# SalinityExpansion.net
KiCad netlist of a schematic drawn in EAGLE
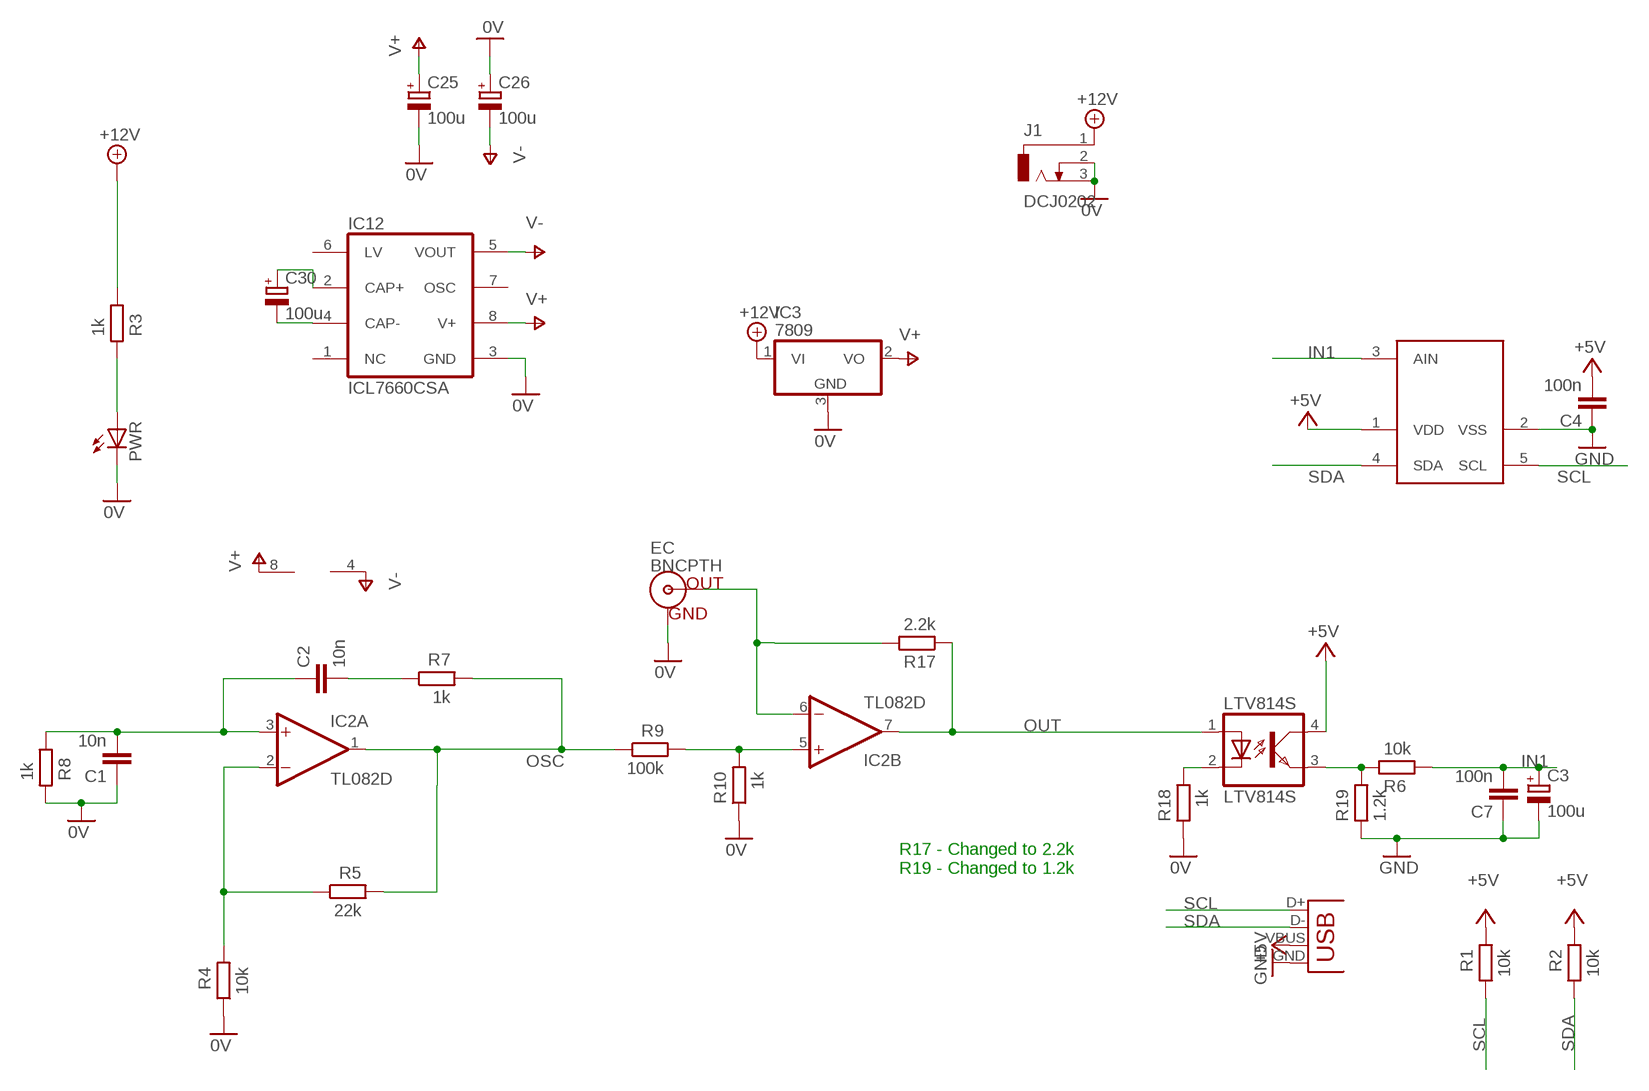
[diagram p0: schematic, sheet 1]

(export (version "E")
  (design (tool "Eeschema 10.0.6"))
  (components
    (comp (ref "C1")
      (value "10n")
      (footprint "eagle-import:C0805K")
      (libsource (lib "eagle-import") (part "C-EUC0805K"))
    )
    (comp (ref "C2")
      (value "10n")
      (footprint "eagle-import:C0805K")
      (libsource (lib "eagle-import") (part "C-EUC0805K"))
    )
    (comp (ref "C3")
      (value "100u")
      (footprint "eagle-import:PANASONIC_D")
      (libsource (lib "eagle-import") (part "CPOL-EUD"))
    )
    (comp (ref "C4")
      (value "100n")
      (footprint "eagle-import:C0805K")
      (libsource (lib "eagle-import") (part "C-EUC0805K"))
    )
    (comp (ref "C7")
      (value "100n")
      (footprint "eagle-import:C0805K")
      (libsource (lib "eagle-import") (part "C-EUC0805K"))
    )
    (comp (ref "C25")
      (value "100u")
      (footprint "eagle-import:PANASONIC_D")
      (libsource (lib "eagle-import") (part "CPOL-EUD"))
    )
    (comp (ref "C26")
      (value "100u")
      (footprint "eagle-import:PANASONIC_D")
      (libsource (lib "eagle-import") (part "CPOL-EUD"))
    )
    (comp (ref "C30")
      (value "100u")
      (footprint "eagle-import:PANASONIC_D")
      (libsource (lib "eagle-import") (part "CPOL-EUD"))
    )
    (comp (ref "EC")
      (value "BNCPTH")
      (footprint "eagle-import:BNC")
      (libsource (lib "eagle-import") (part "BNCPTH"))
    )
    (comp (ref "IC2")
      (value "TL082D")
      (footprint "eagle-import:SO08")
      (libsource (lib "eagle-import") (part "TL082D"))
    )
    (comp (ref "IC3")
      (value "7809")
      (footprint "eagle-import:TO252")
      (libsource (lib "eagle-import") (part "78DT05"))
    )
    (comp (ref "IC12")
      (value "ICL7660CSA")
      (footprint "eagle-import:SO08")
      (fields (field (name "MF") "MAXIM"))
      (libsource (lib "eagle-import") (part "ICL7660CSA"))
    )
    (comp (ref "J1")
      (value "DCJ0202")
      (footprint "eagle-import:DCJ0202")
      (libsource (lib "eagle-import") (part "DCJ0202"))
    )
    (comp (ref "LTV814S")
      (value "LTV814S")
      (footprint "eagle-import:SMD4")
      (libsource (lib "eagle-import") (part "LTV816S"))
    )
    (comp (ref "PWR")
      (value "LED3MM")
      (footprint "eagle-import:LED3MM")
      (libsource (lib "eagle-import") (part "LED3MM"))
    )
    (comp (ref "R1")
      (value "10k")
      (footprint "eagle-import:R0805")
      (libsource (lib "eagle-import") (part "R-EU_R0805"))
    )
    (comp (ref "R2")
      (value "10k")
      (footprint "eagle-import:R0805")
      (libsource (lib "eagle-import") (part "R-EU_R0805"))
    )
    (comp (ref "R3")
      (value "1k")
      (footprint "eagle-import:R0805")
      (libsource (lib "eagle-import") (part "R-EU_R0805"))
    )
    (comp (ref "R4")
      (value "10k")
      (footprint "eagle-import:R0805")
      (libsource (lib "eagle-import") (part "R-EU_R0805"))
    )
    (comp (ref "R5")
      (value "22k")
      (footprint "eagle-import:R0805")
      (libsource (lib "eagle-import") (part "R-EU_R0805"))
    )
    (comp (ref "R6")
      (value "10k")
      (footprint "eagle-import:R0805")
      (libsource (lib "eagle-import") (part "R-EU_R0805"))
    )
    (comp (ref "R7")
      (value "1k")
      (footprint "eagle-import:R0805")
      (libsource (lib "eagle-import") (part "R-EU_R0805"))
    )
    (comp (ref "R8")
      (value "1k")
      (footprint "eagle-import:R0805")
      (libsource (lib "eagle-import") (part "R-EU_R0805"))
    )
    (comp (ref "R9")
      (value "100k")
      (footprint "eagle-import:R0805")
      (libsource (lib "eagle-import") (part "R-EU_R0805"))
    )
    (comp (ref "R10")
      (value "1k")
      (footprint "eagle-import:R0805")
      (libsource (lib "eagle-import") (part "R-EU_R0805"))
    )
    (comp (ref "R17")
      (value "2.2k")
      (footprint "eagle-import:R0805")
      (libsource (lib "eagle-import") (part "R-EU_R0805"))
    )
    (comp (ref "R18")
      (value "1k")
      (footprint "eagle-import:R0805")
      (libsource (lib "eagle-import") (part "R-EU_R0805"))
    )
    (comp (ref "R19")
      (value "1.2k")
      (footprint "eagle-import:R0805")
      (libsource (lib "eagle-import") (part "R-EU_R0805"))
    )
    (comp (ref "U$2")
      (value "MCP3221")
      (footprint "eagle-import:SOT23-5")
      (libsource (lib "eagle-import") (part "MCP3221"))
    )
    (comp (ref "X5")
      (value "USBSMD")
      (footprint "eagle-import:USB-MINIB")
      (libsource (lib "eagle-import") (part "USBSMD"))
    )
  )
  (nets
    (net (code "1") (name "+5V") (class "Default")
      (node (ref "C4") (pin "2") (pinfunction "2_2") (pintype "passive"))
      (node (ref "LTV814S") (pin "4") (pinfunction "COL_4") (pintype "passive"))
      (node (ref "R1") (pin "2") (pinfunction "2_2") (pintype "passive"))
      (node (ref "R2") (pin "2") (pinfunction "2_2") (pintype "passive"))
      (node (ref "U$2") (pin "1") (pinfunction "VDD_1") (pintype "bidirectional"))
      (node (ref "X5") (pin "VBUS") (pinfunction "VBUS_VBUS") (pintype "bidirectional"))
    )
    (net (code "2") (name "+12V") (class "Default")
      (node (ref "IC3") (pin "1") (pinfunction "VI_1") (pintype "input"))
      (node (ref "J1") (pin "1") (pinfunction "1_1") (pintype "passive"))
      (node (ref "R3") (pin "1") (pinfunction "1_1") (pintype "passive"))
    )
    (net (code "3") (name "/IN1") (class "Default")
      (node (ref "C3") (pin "+") (pinfunction "+_+") (pintype "passive"))
      (node (ref "C7") (pin "2") (pinfunction "2_2") (pintype "passive"))
      (node (ref "R6") (pin "1") (pinfunction "1_1") (pintype "passive"))
      (node (ref "U$2") (pin "3") (pinfunction "AIN_3") (pintype "bidirectional"))
    )
    (net (code "4") (name "/OSC") (class "Default")
      (node (ref "IC2") (pin "1") (pinfunction "OUT_1") (pintype "output"))
      (node (ref "R5") (pin "2") (pinfunction "2_2") (pintype "passive"))
      (node (ref "R7") (pin "2") (pinfunction "2_2") (pintype "passive"))
      (node (ref "R9") (pin "1") (pinfunction "1_1") (pintype "passive"))
    )
    (net (code "5") (name "/OUT") (class "Default")
      (node (ref "IC2") (pin "7") (pinfunction "OUT_7") (pintype "output"))
      (node (ref "LTV814S") (pin "1") (pinfunction "A_1") (pintype "passive"))
      (node (ref "R17") (pin "1") (pinfunction "1_1") (pintype "passive"))
    )
    (net (code "6") (name "/SCL") (class "Default")
      (node (ref "R1") (pin "1") (pinfunction "1_1") (pintype "passive"))
      (node (ref "U$2") (pin "5") (pinfunction "SCL_5") (pintype "bidirectional"))
      (node (ref "X5") (pin "D+") (pinfunction "D+_D+") (pintype "bidirectional"))
    )
    (net (code "7") (name "/SDA") (class "Default")
      (node (ref "R2") (pin "1") (pinfunction "1_1") (pintype "passive"))
      (node (ref "U$2") (pin "4") (pinfunction "SDA_4") (pintype "bidirectional"))
      (node (ref "X5") (pin "D-") (pinfunction "D-_D-") (pintype "bidirectional"))
    )
    (net (code "8") (name "0V") (class "Default")
      (node (ref "C1") (pin "1") (pinfunction "1_1") (pintype "passive"))
      (node (ref "C25") (pin "-") (pinfunction "-_-") (pintype "passive"))
      (node (ref "C26") (pin "+") (pinfunction "+_+") (pintype "passive"))
      (node (ref "EC") (pin "GND") (pinfunction "GND_GND") (pintype "bidirectional"))
      (node (ref "IC12") (pin "3") (pinfunction "GND_3") (pintype "power_in"))
      (node (ref "IC3") (pin "3") (pinfunction "GND_3") (pintype "passive"))
      (node (ref "J1") (pin "2") (pinfunction "2_2") (pintype "passive"))
      (node (ref "J1") (pin "3") (pinfunction "3_3") (pintype "passive"))
      (node (ref "PWR") (pin "K") (pinfunction "C_K") (pintype "passive"))
      (node (ref "R10") (pin "1") (pinfunction "1_1") (pintype "passive"))
      (node (ref "R18") (pin "1") (pinfunction "1_1") (pintype "passive"))
      (node (ref "R4") (pin "1") (pinfunction "1_1") (pintype "passive"))
      (node (ref "R8") (pin "2") (pinfunction "2_2") (pintype "passive"))
    )
    (net (code "9") (name "GND") (class "Default")
      (node (ref "C3") (pin "-") (pinfunction "-_-") (pintype "passive"))
      (node (ref "C4") (pin "1") (pinfunction "1_1") (pintype "passive"))
      (node (ref "C7") (pin "1") (pinfunction "1_1") (pintype "passive"))
      (node (ref "R19") (pin "1") (pinfunction "1_1") (pintype "passive"))
      (node (ref "U$2") (pin "2") (pinfunction "VSS_2") (pintype "bidirectional"))
      (node (ref "X5") (pin "GND") (pinfunction "GND_GND") (pintype "bidirectional"))
    )
    (net (code "10") (name "Net-(C2-Pad2)") (class "Default")
      (node (ref "C2") (pin "2") (pinfunction "2_2") (pintype "passive"))
      (node (ref "R7") (pin "1") (pinfunction "1_1") (pintype "passive"))
    )
    (net (code "11") (name "Net-(EC-OUT)") (class "Default")
      (node (ref "EC") (pin "S") (pinfunction "OUT_S") (pintype "bidirectional"))
      (node (ref "IC2") (pin "6") (pinfunction "-IN_6") (pintype "input"))
      (node (ref "R17") (pin "2") (pinfunction "2_2") (pintype "passive"))
    )
    (net (code "12") (name "Net-(IC2A-+IN)") (class "Default")
      (node (ref "C1") (pin "2") (pinfunction "2_2") (pintype "passive"))
      (node (ref "C2") (pin "1") (pinfunction "1_1") (pintype "passive"))
      (node (ref "IC2") (pin "3") (pinfunction "+IN_3") (pintype "input"))
      (node (ref "R8") (pin "1") (pinfunction "1_1") (pintype "passive"))
    )
    (net (code "13") (name "Net-(IC2A--IN)") (class "Default")
      (node (ref "IC2") (pin "2") (pinfunction "-IN_2") (pintype "input"))
      (node (ref "R4") (pin "2") (pinfunction "2_2") (pintype "passive"))
      (node (ref "R5") (pin "1") (pinfunction "1_1") (pintype "passive"))
    )
    (net (code "14") (name "Net-(IC2B-+IN)") (class "Default")
      (node (ref "IC2") (pin "5") (pinfunction "+IN_5") (pintype "input"))
      (node (ref "R10") (pin "2") (pinfunction "2_2") (pintype "passive"))
      (node (ref "R9") (pin "2") (pinfunction "2_2") (pintype "passive"))
    )
    (net (code "15") (name "Net-(IC12-CAP+)") (class "Default")
      (node (ref "C30") (pin "+") (pinfunction "+_+") (pintype "passive"))
      (node (ref "IC12") (pin "2") (pinfunction "CAP+_2") (pintype "passive"))
    )
    (net (code "16") (name "Net-(IC12-CAP-)") (class "Default")
      (node (ref "C30") (pin "-") (pinfunction "-_-") (pintype "passive"))
      (node (ref "IC12") (pin "4") (pinfunction "CAP-_4") (pintype "passive"))
    )
    (net (code "17") (name "Net-(LTV814S-C)") (class "Default")
      (node (ref "LTV814S") (pin "2") (pinfunction "C_2") (pintype "passive"))
      (node (ref "R18") (pin "2") (pinfunction "2_2") (pintype "passive"))
    )
    (net (code "18") (name "Net-(LTV814S-EMIT)") (class "Default")
      (node (ref "LTV814S") (pin "3") (pinfunction "EMIT_3") (pintype "passive"))
      (node (ref "R19") (pin "2") (pinfunction "2_2") (pintype "passive"))
      (node (ref "R6") (pin "2") (pinfunction "2_2") (pintype "passive"))
    )
    (net (code "19") (name "Net-(PWR-PadA)") (class "Default")
      (node (ref "PWR") (pin "A") (pinfunction "A_A") (pintype "passive"))
      (node (ref "R3") (pin "2") (pinfunction "2_2") (pintype "passive"))
    )
    (net (code "20") (name "V+") (class "Default")
      (node (ref "C25") (pin "+") (pinfunction "+_+") (pintype "passive"))
      (node (ref "IC12") (pin "8") (pinfunction "V+_8") (pintype "power_in"))
      (node (ref "IC2") (pin "8") (pinfunction "V+_8") (pintype "power_in"))
      (node (ref "IC3") (pin "2") (pinfunction "VO_2") (pintype "passive"))
    )
    (net (code "21") (name "V-") (class "Default")
      (node (ref "C26") (pin "-") (pinfunction "-_-") (pintype "passive"))
      (node (ref "IC12") (pin "5") (pinfunction "VOUT_5") (pintype "output"))
      (node (ref "IC2") (pin "4") (pinfunction "V-_4") (pintype "power_in"))
    )
    (net (code "22") (name "unconnected-(IC12-LV-Pad6)") (class "Default")
      (node (ref "IC12") (pin "6") (pinfunction "LV_6") (pintype "passive"))
    )
    (net (code "23") (name "unconnected-(IC12-NC-Pad1)") (class "Default")
      (node (ref "IC12") (pin "1") (pinfunction "NC_1") (pintype "no_connect"))
    )
    (net (code "24") (name "unconnected-(IC12-OSC-Pad7)") (class "Default")
      (node (ref "IC12") (pin "7") (pinfunction "OSC_7") (pintype "output"))
    )
  )
)
